# untitled.net
KiCad netlist of a schematic drawn in EAGLE
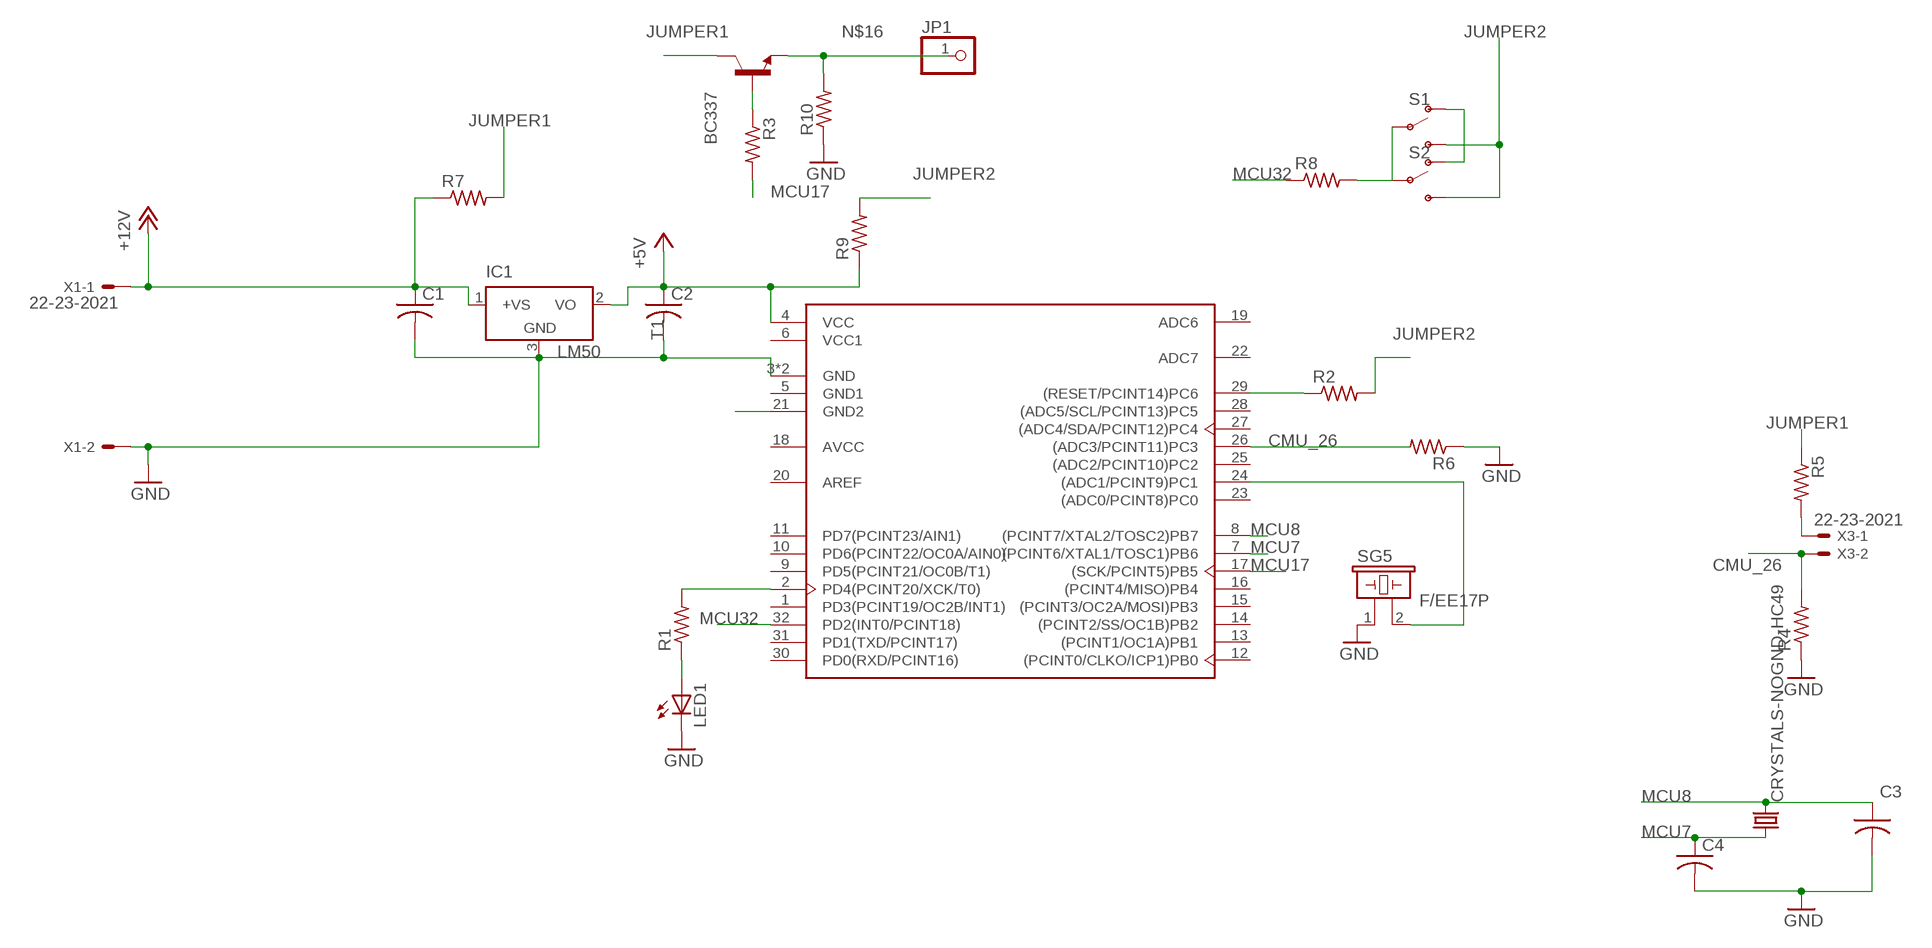
[diagram p0: schematic, sheet 1]

(export (version "E")
  (design (tool "Eeschema 10.0.6"))
  (components
    (comp (ref "C1")
      (value "C-USC1206K")
      (footprint "eagle-import:C1206K")
      (libsource (lib "eagle-import") (part "C-USC1206K"))
    )
    (comp (ref "C2")
      (value "C-USC1206K")
      (footprint "eagle-import:C1206K")
      (libsource (lib "eagle-import") (part "C-USC1206K"))
    )
    (comp (ref "C3")
      (value "C-USC0603K")
      (footprint "eagle-import:C0603K")
      (libsource (lib "eagle-import") (part "C-USC0603K"))
    )
    (comp (ref "C4")
      (value "C-USC0603K")
      (footprint "eagle-import:C0603K")
      (libsource (lib "eagle-import") (part "C-USC0603K"))
    )
    (comp (ref "IC1")
      (value "LM50")
      (footprint "eagle-import:SOT23")
      (libsource (lib "eagle-import") (part "LM50"))
    )
    (comp (ref "JP1")
      (value "PINHD-1X1")
      (footprint "eagle-import:1X01")
      (libsource (lib "eagle-import") (part "PINHD-1X1"))
    )
    (comp (ref "LED1")
      (value "LED3MM")
      (footprint "eagle-import:LED3MM")
      (libsource (lib "eagle-import") (part "LED3MM"))
    )
    (comp (ref "R1")
      (value "R-US_0204/7")
      (footprint "eagle-import:0204_7")
      (libsource (lib "eagle-import") (part "R-US_0204/7"))
    )
    (comp (ref "R2")
      (value "R-US_R0603")
      (footprint "eagle-import:R0603")
      (libsource (lib "eagle-import") (part "R-US_R0603"))
    )
    (comp (ref "R3")
      (value "R-US_0204/7")
      (footprint "eagle-import:0204_7")
      (libsource (lib "eagle-import") (part "R-US_0204/7"))
    )
    (comp (ref "R4")
      (value "R-US_0204/7")
      (footprint "eagle-import:0204_7")
      (libsource (lib "eagle-import") (part "R-US_0204/7"))
    )
    (comp (ref "R5")
      (value "R-US_0204/7")
      (footprint "eagle-import:0204_7")
      (libsource (lib "eagle-import") (part "R-US_0204/7"))
    )
    (comp (ref "R6")
      (value "R-US_0204/7")
      (footprint "eagle-import:0204_7")
      (libsource (lib "eagle-import") (part "R-US_0204/7"))
    )
    (comp (ref "R7")
      (value "R-US_0204/7")
      (footprint "eagle-import:0204_7")
      (libsource (lib "eagle-import") (part "R-US_0204/7"))
    )
    (comp (ref "R8")
      (value "R-US_0204/7")
      (footprint "eagle-import:0204_7")
      (libsource (lib "eagle-import") (part "R-US_0204/7"))
    )
    (comp (ref "R9")
      (value "R-US_0204/7")
      (footprint "eagle-import:0204_7")
      (libsource (lib "eagle-import") (part "R-US_0204/7"))
    )
    (comp (ref "R10")
      (value "R-US_0204/7")
      (footprint "eagle-import:0204_7")
      (libsource (lib "eagle-import") (part "R-US_0204/7"))
    )
    (comp (ref "S1")
      (value "SWITCH-SPDT-PTH-11.6X4.0MM-LOCK")
      (footprint "eagle-import:SWITCH_SPDT_PTH_11.6X4.0MM_LOCK")
      (libsource (lib "eagle-import") (part "SWITCH-SPDT-PTH-11.6X4.0MM-LOCK"))
    )
    (comp (ref "S2")
      (value "SWITCH-SPDT-PTH-11.6X4.0MM-LOCK")
      (footprint "eagle-import:SWITCH_SPDT_PTH_11.6X4.0MM_LOCK")
      (libsource (lib "eagle-import") (part "SWITCH-SPDT-PTH-11.6X4.0MM-LOCK"))
    )
    (comp (ref "SG5")
      (value "F/EE17P")
      (footprint "eagle-import:F_EE17P")
      (libsource (lib "eagle-import") (part "F/EE17P"))
    )
    (comp (ref "T1")
      (value "BC337")
      (footprint "eagle-import:TO92")
      (libsource (lib "eagle-import") (part "BC337"))
    )
    (comp (ref "U1")
      (value "ATMEGA328P-MU")
      (footprint "eagle-import:VQFN-32")
      (fields
        (field (name "DIGIKEY_PART_NUMBER") "ATMEGA328P-MU-ND")
        (field (name "MANUFACTURER") "Microchip Technology")
        (field (name "CREATED_BY") "PCBLayout.com")
      )
      (libsource (lib "eagle-import") (part "ATMEGA328P-MU"))
    )
    (comp (ref "X1")
      (value "22-23-2021")
      (footprint "eagle-import:22-23-2021")
      (fields (field (name "MF") "MOLEX"))
      (libsource (lib "eagle-import") (part "22-23-2021"))
    )
    (comp (ref "X2")
      (value "CRYSTALS-NOGND-HC49")
      (footprint "eagle-import:HC49")
      (libsource (lib "eagle-import") (part "CRYSTALS-NOGND-HC49"))
    )
    (comp (ref "X3")
      (value "22-23-2021")
      (footprint "eagle-import:22-23-2021")
      (fields (field (name "MF") "MOLEX"))
      (libsource (lib "eagle-import") (part "22-23-2021"))
    )
  )
  (nets
    (net (code "1") (name "+5V") (class "Default")
      (node (ref "C2") (pin "1") (pinfunction "1_1") (pintype "passive"))
      (node (ref "IC1") (pin "2") (pinfunction "VO_2") (pintype "input"))
      (node (ref "R9") (pin "1") (pinfunction "1_1") (pintype "passive"))
      (node (ref "U1") (pin "4") (pinfunction "VCC_4") (pintype "power_in"))
    )
    (net (code "2") (name "+12V") (class "Default")
      (node (ref "C1") (pin "1") (pinfunction "1_1") (pintype "passive"))
      (node (ref "IC1") (pin "1") (pinfunction "+VS_1") (pintype "input"))
      (node (ref "R7") (pin "1") (pinfunction "1_1") (pintype "passive"))
      (node (ref "X1") (pin "1") (pinfunction "S_1") (pintype "passive"))
    )
    (net (code "3") (name "/AREF") (class "Default")
      (node (ref "U1") (pin "20") (pinfunction "AREF_20") (pintype "power_in"))
    )
    (net (code "4") (name "/AVCC") (class "Default")
      (node (ref "U1") (pin "18") (pinfunction "AVCC_18") (pintype "power_in"))
    )
    (net (code "5") (name "/CMU_26") (class "Default")
      (node (ref "R4") (pin "2") (pinfunction "2_2") (pintype "passive"))
      (node (ref "R6") (pin "2") (pinfunction "2_2") (pintype "passive"))
      (node (ref "U1") (pin "26") (pinfunction "(ADC3/PCINT11)PC3_26") (pintype "bidirectional"))
      (node (ref "X3") (pin "2") (pinfunction "S_2") (pintype "passive"))
    )
    (net (code "6") (name "/GND1") (class "Default")
      (node (ref "U1") (pin "5") (pinfunction "GND1_5") (pintype "power_in"))
    )
    (net (code "7") (name "/JUMPER1") (class "Default")
      (node (ref "R5") (pin "1") (pinfunction "1_1") (pintype "passive"))
      (node (ref "R7") (pin "2") (pinfunction "2_2") (pintype "passive"))
      (node (ref "T1") (pin "3") (pinfunction "C_3") (pintype "passive"))
    )
    (net (code "8") (name "/JUMPER2") (class "Default")
      (node (ref "R2") (pin "2") (pinfunction "2_2") (pintype "passive"))
      (node (ref "R9") (pin "2") (pinfunction "2_2") (pintype "passive"))
      (node (ref "S1") (pin "3") (pinfunction "S_3") (pintype "passive"))
      (node (ref "S2") (pin "3") (pinfunction "S_3") (pintype "passive"))
    )
    (net (code "9") (name "/MCU7") (class "Default")
      (node (ref "C4") (pin "1") (pinfunction "1_1") (pintype "passive"))
      (node (ref "U1") (pin "7") (pinfunction "(PCINT6/XTAL1/TOSC1)PB6_7") (pintype "bidirectional"))
      (node (ref "X2") (pin "1") (pinfunction "1_1") (pintype "passive"))
    )
    (net (code "10") (name "/MCU8") (class "Default")
      (node (ref "C3") (pin "1") (pinfunction "1_1") (pintype "passive"))
      (node (ref "U1") (pin "8") (pinfunction "(PCINT7/XTAL2/TOSC2)PB7_8") (pintype "bidirectional"))
      (node (ref "X2") (pin "2") (pinfunction "2_2") (pintype "passive"))
    )
    (net (code "11") (name "/MCU17") (class "Default")
      (node (ref "R3") (pin "2") (pinfunction "2_2") (pintype "passive"))
      (node (ref "U1") (pin "17") (pinfunction "(SCK/PCINT5)PB5_17") (pintype "bidirectional"))
    )
    (net (code "12") (name "/MCU32") (class "Default")
      (node (ref "U1") (pin "32") (pinfunction "PD2(INT0/PCINT18)_32") (pintype "bidirectional"))
    )
    (net (code "13") (name "/N$16") (class "Default")
      (node (ref "JP1") (pin "1") (pinfunction "1_1") (pintype "passive"))
      (node (ref "R10") (pin "2") (pinfunction "2_2") (pintype "passive"))
      (node (ref "T1") (pin "1") (pinfunction "E_1") (pintype "passive"))
    )
    (net (code "14") (name "/VCC1") (class "Default")
      (node (ref "U1") (pin "6") (pinfunction "VCC1_6") (pintype "power_in"))
    )
    (net (code "15") (name "GND") (class "Default")
      (node (ref "C1") (pin "2") (pinfunction "2_2") (pintype "passive"))
      (node (ref "C2") (pin "2") (pinfunction "2_2") (pintype "passive"))
      (node (ref "C3") (pin "2") (pinfunction "2_2") (pintype "passive"))
      (node (ref "C4") (pin "2") (pinfunction "2_2") (pintype "passive"))
      (node (ref "IC1") (pin "3") (pinfunction "GND_3") (pintype "power_in"))
      (node (ref "LED1") (pin "K") (pinfunction "C_K") (pintype "passive"))
      (node (ref "R10") (pin "1") (pinfunction "1_1") (pintype "passive"))
      (node (ref "R4") (pin "1") (pinfunction "1_1") (pintype "passive"))
      (node (ref "R6") (pin "1") (pinfunction "1_1") (pintype "passive"))
      (node (ref "SG5") (pin "1") (pinfunction "1_1") (pintype "passive"))
      (node (ref "U1") (pin "3") (pinfunction "GND_3") (pintype "power_in"))
      (node (ref "U1") (pin "33") (pinfunction "GND_33") (pintype "power_in"))
      (node (ref "X1") (pin "2") (pinfunction "S_2") (pintype "passive"))
    )
    (net (code "16") (name "Net-(LED1-PadA)") (class "Default")
      (node (ref "LED1") (pin "A") (pinfunction "A_A") (pintype "passive"))
      (node (ref "R1") (pin "1") (pinfunction "1_1") (pintype "passive"))
    )
    (net (code "17") (name "Net-(S1-O)") (class "Default")
      (node (ref "S1") (pin "1") (pinfunction "O_1") (pintype "passive"))
      (node (ref "S2") (pin "1") (pinfunction "O_1") (pintype "passive"))
    )
    (net (code "18") (name "Net-(S1-P)") (class "Default")
      (node (ref "R8") (pin "2") (pinfunction "2_2") (pintype "passive"))
      (node (ref "S1") (pin "2") (pinfunction "P_2") (pintype "passive"))
      (node (ref "S2") (pin "2") (pinfunction "P_2") (pintype "passive"))
    )
    (net (code "19") (name "Net-(T1-B)") (class "Default")
      (node (ref "R3") (pin "1") (pinfunction "1_1") (pintype "passive"))
      (node (ref "T1") (pin "2") (pinfunction "B_2") (pintype "passive"))
    )
    (net (code "20") (name "Net-(U1-(ADC1{slash}PCINT9)PC1)") (class "Default")
      (node (ref "SG5") (pin "2") (pinfunction "2_2") (pintype "passive"))
      (node (ref "U1") (pin "24") (pinfunction "(ADC1/PCINT9)PC1_24") (pintype "bidirectional"))
    )
    (net (code "21") (name "Net-(U1-(RESET{slash}PCINT14)PC6)") (class "Default")
      (node (ref "R2") (pin "1") (pinfunction "1_1") (pintype "passive"))
      (node (ref "U1") (pin "29") (pinfunction "(RESET/PCINT14)PC6_29") (pintype "bidirectional"))
    )
    (net (code "22") (name "Net-(U1-PD4(PCINT20{slash}XCK{slash}T0))") (class "Default")
      (node (ref "R1") (pin "2") (pinfunction "2_2") (pintype "passive"))
      (node (ref "U1") (pin "2") (pinfunction "PD4(PCINT20/XCK/T0)_2") (pintype "bidirectional"))
    )
    (net (code "23") (name "Net-(X3A-S)") (class "Default")
      (node (ref "R5") (pin "2") (pinfunction "2_2") (pintype "passive"))
      (node (ref "X3") (pin "1") (pinfunction "S_1") (pintype "passive"))
    )
    (net (code "24") (name "unconnected-(R8-Pad1)") (class "Default")
      (node (ref "R8") (pin "1") (pinfunction "1_1") (pintype "passive"))
    )
    (net (code "25") (name "unconnected-(U1-(ADC0{slash}PCINT8)PC0-Pad23)") (class "Default")
      (node (ref "U1") (pin "23") (pinfunction "(ADC0/PCINT8)PC0_23") (pintype "bidirectional"))
    )
    (net (code "26") (name "unconnected-(U1-(ADC2{slash}PCINT10)PC2-Pad25)") (class "Default")
      (node (ref "U1") (pin "25") (pinfunction "(ADC2/PCINT10)PC2_25") (pintype "bidirectional"))
    )
    (net (code "27") (name "unconnected-(U1-(ADC4{slash}SDA{slash}PCINT12)PC4-Pad27)") (class "Default")
      (node (ref "U1") (pin "27") (pinfunction "(ADC4/SDA/PCINT12)PC4_27") (pintype "bidirectional"))
    )
    (net (code "28") (name "unconnected-(U1-(ADC5{slash}SCL{slash}PCINT13)PC5-Pad28)") (class "Default")
      (node (ref "U1") (pin "28") (pinfunction "(ADC5/SCL/PCINT13)PC5_28") (pintype "bidirectional"))
    )
    (net (code "29") (name "unconnected-(U1-(PCINT0{slash}CLKO{slash}ICP1)PB0-Pad12)") (class "Default")
      (node (ref "U1") (pin "12") (pinfunction "(PCINT0/CLKO/ICP1)PB0_12") (pintype "bidirectional"))
    )
    (net (code "30") (name "unconnected-(U1-(PCINT1{slash}OC1A)PB1-Pad13)") (class "Default")
      (node (ref "U1") (pin "13") (pinfunction "(PCINT1/OC1A)PB1_13") (pintype "bidirectional"))
    )
    (net (code "31") (name "unconnected-(U1-(PCINT2{slash}SS{slash}OC1B)PB2-Pad14)") (class "Default")
      (node (ref "U1") (pin "14") (pinfunction "(PCINT2/SS/OC1B)PB2_14") (pintype "bidirectional"))
    )
    (net (code "32") (name "unconnected-(U1-(PCINT3{slash}OC2A{slash}MOSI)PB3-Pad15)") (class "Default")
      (node (ref "U1") (pin "15") (pinfunction "(PCINT3/OC2A/MOSI)PB3_15") (pintype "bidirectional"))
    )
    (net (code "33") (name "unconnected-(U1-(PCINT4{slash}MISO)PB4-Pad16)") (class "Default")
      (node (ref "U1") (pin "16") (pinfunction "(PCINT4/MISO)PB4_16") (pintype "bidirectional"))
    )
    (net (code "34") (name "unconnected-(U1-ADC6-Pad19)") (class "Default")
      (node (ref "U1") (pin "19") (pinfunction "ADC6_19") (pintype "input"))
    )
    (net (code "35") (name "unconnected-(U1-ADC7-Pad22)") (class "Default")
      (node (ref "U1") (pin "22") (pinfunction "ADC7_22") (pintype "input"))
    )
    (net (code "36") (name "unconnected-(U1-GND2-Pad21)") (class "Default")
      (node (ref "U1") (pin "21") (pinfunction "GND2_21") (pintype "power_in"))
    )
    (net (code "37") (name "unconnected-(U1-PD0(RXD{slash}PCINT16)-Pad30)") (class "Default")
      (node (ref "U1") (pin "30") (pinfunction "PD0(RXD/PCINT16)_30") (pintype "bidirectional"))
    )
    (net (code "38") (name "unconnected-(U1-PD1(TXD{slash}PCINT17)-Pad31)") (class "Default")
      (node (ref "U1") (pin "31") (pinfunction "PD1(TXD/PCINT17)_31") (pintype "bidirectional"))
    )
    (net (code "39") (name "unconnected-(U1-PD3(PCINT19{slash}OC2B{slash}INT1)-Pad1)") (class "Default")
      (node (ref "U1") (pin "1") (pinfunction "PD3(PCINT19/OC2B/INT1)_1") (pintype "bidirectional"))
    )
    (net (code "40") (name "unconnected-(U1-PD5(PCINT21{slash}OC0B{slash}T1)-Pad9)") (class "Default")
      (node (ref "U1") (pin "9") (pinfunction "PD5(PCINT21/OC0B/T1)_9") (pintype "bidirectional"))
    )
    (net (code "41") (name "unconnected-(U1-PD6(PCINT22{slash}OC0A{slash}AIN0)-Pad10)") (class "Default")
      (node (ref "U1") (pin "10") (pinfunction "PD6(PCINT22/OC0A/AIN0)_10") (pintype "bidirectional"))
    )
    (net (code "42") (name "unconnected-(U1-PD7(PCINT23{slash}AIN1)-Pad11)") (class "Default")
      (node (ref "U1") (pin "11") (pinfunction "PD7(PCINT23/AIN1)_11") (pintype "bidirectional"))
    )
  )
)
